# ADC_Board_Single_Board.net
KiCad netlist of a schematic drawn in EAGLE
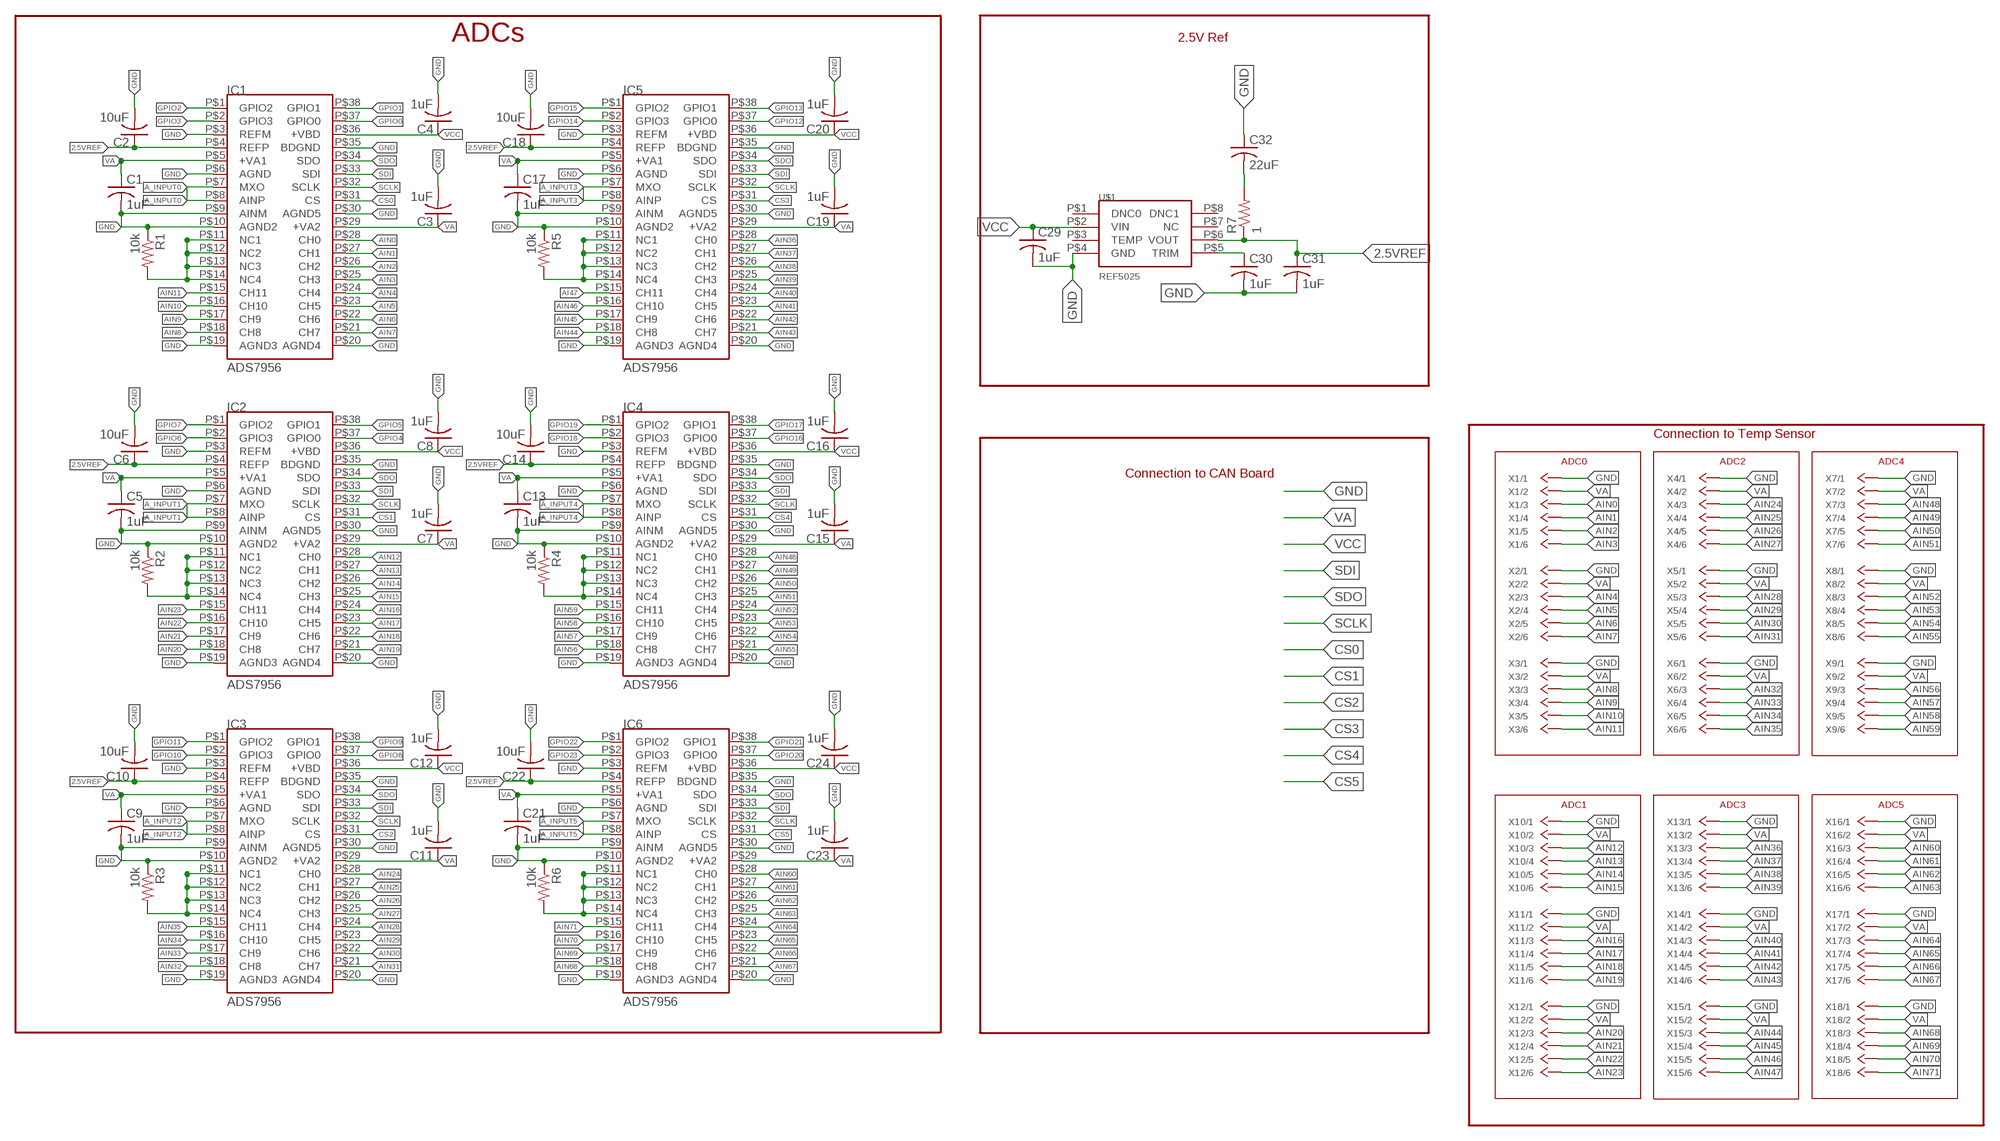
[diagram p0: schematic, sheet 1]

(export (version "E")
  (design (tool "Eeschema 10.0.6"))
  (components
    (comp (ref "C1")
      (value "1uF")
      (footprint "eagle-import:C0603")
      (libsource (lib "eagle-import") (part "C-USC0603"))
    )
    (comp (ref "C2")
      (value "10uF")
      (footprint "eagle-import:C0603")
      (libsource (lib "eagle-import") (part "C-USC0603"))
    )
    (comp (ref "C3")
      (value "1uF")
      (footprint "eagle-import:C0603")
      (libsource (lib "eagle-import") (part "C-USC0603"))
    )
    (comp (ref "C4")
      (value "1uF")
      (footprint "eagle-import:C0603")
      (libsource (lib "eagle-import") (part "C-USC0603"))
    )
    (comp (ref "C5")
      (value "1uF")
      (footprint "eagle-import:C0603")
      (libsource (lib "eagle-import") (part "C-USC0603"))
    )
    (comp (ref "C6")
      (value "10uF")
      (footprint "eagle-import:C0603")
      (libsource (lib "eagle-import") (part "C-USC0603"))
    )
    (comp (ref "C7")
      (value "1uF")
      (footprint "eagle-import:C0603")
      (libsource (lib "eagle-import") (part "C-USC0603"))
    )
    (comp (ref "C8")
      (value "1uF")
      (footprint "eagle-import:C0603")
      (libsource (lib "eagle-import") (part "C-USC0603"))
    )
    (comp (ref "C9")
      (value "1uF")
      (footprint "eagle-import:C0603")
      (libsource (lib "eagle-import") (part "C-USC0603"))
    )
    (comp (ref "C10")
      (value "10uF")
      (footprint "eagle-import:C0603")
      (libsource (lib "eagle-import") (part "C-USC0603"))
    )
    (comp (ref "C11")
      (value "1uF")
      (footprint "eagle-import:C0603")
      (libsource (lib "eagle-import") (part "C-USC0603"))
    )
    (comp (ref "C12")
      (value "1uF")
      (footprint "eagle-import:C0603")
      (libsource (lib "eagle-import") (part "C-USC0603"))
    )
    (comp (ref "C13")
      (value "1uF")
      (footprint "eagle-import:C0603")
      (libsource (lib "eagle-import") (part "C-USC0603"))
    )
    (comp (ref "C14")
      (value "10uF")
      (footprint "eagle-import:C0603")
      (libsource (lib "eagle-import") (part "C-USC0603"))
    )
    (comp (ref "C15")
      (value "1uF")
      (footprint "eagle-import:C0603")
      (libsource (lib "eagle-import") (part "C-USC0603"))
    )
    (comp (ref "C16")
      (value "1uF")
      (footprint "eagle-import:C0603")
      (libsource (lib "eagle-import") (part "C-USC0603"))
    )
    (comp (ref "C17")
      (value "1uF")
      (footprint "eagle-import:C0603")
      (libsource (lib "eagle-import") (part "C-USC0603"))
    )
    (comp (ref "C18")
      (value "10uF")
      (footprint "eagle-import:C0603")
      (libsource (lib "eagle-import") (part "C-USC0603"))
    )
    (comp (ref "C19")
      (value "1uF")
      (footprint "eagle-import:C0603")
      (libsource (lib "eagle-import") (part "C-USC0603"))
    )
    (comp (ref "C20")
      (value "1uF")
      (footprint "eagle-import:C0603")
      (libsource (lib "eagle-import") (part "C-USC0603"))
    )
    (comp (ref "C21")
      (value "1uF")
      (footprint "eagle-import:C0603")
      (libsource (lib "eagle-import") (part "C-USC0603"))
    )
    (comp (ref "C22")
      (value "10uF")
      (footprint "eagle-import:C0603")
      (libsource (lib "eagle-import") (part "C-USC0603"))
    )
    (comp (ref "C23")
      (value "1uF")
      (footprint "eagle-import:C0603")
      (libsource (lib "eagle-import") (part "C-USC0603"))
    )
    (comp (ref "C24")
      (value "1uF")
      (footprint "eagle-import:C0603")
      (libsource (lib "eagle-import") (part "C-USC0603"))
    )
    (comp (ref "C29")
      (value "1uF")
      (footprint "eagle-import:C0603")
      (libsource (lib "eagle-import") (part "C-USC0603"))
    )
    (comp (ref "C30")
      (value "1uF")
      (footprint "eagle-import:C0603")
      (libsource (lib "eagle-import") (part "C-USC0603"))
    )
    (comp (ref "C31")
      (value "1uF")
      (footprint "eagle-import:C0603")
      (libsource (lib "eagle-import") (part "C-USC0603"))
    )
    (comp (ref "C32")
      (value "22uF")
      (footprint "eagle-import:C0603")
      (libsource (lib "eagle-import") (part "C-USC0603"))
    )
    (comp (ref "IC1")
      (value "ADS7956")
      (footprint "eagle-import:TSSOP-38")
      (libsource (lib "eagle-import") (part "ADS7956"))
    )
    (comp (ref "IC2")
      (value "ADS7956")
      (footprint "eagle-import:TSSOP-38")
      (libsource (lib "eagle-import") (part "ADS7956"))
    )
    (comp (ref "IC3")
      (value "ADS7956")
      (footprint "eagle-import:TSSOP-38")
      (libsource (lib "eagle-import") (part "ADS7956"))
    )
    (comp (ref "IC4")
      (value "ADS7956")
      (footprint "eagle-import:TSSOP-38")
      (libsource (lib "eagle-import") (part "ADS7956"))
    )
    (comp (ref "IC5")
      (value "ADS7956")
      (footprint "eagle-import:TSSOP-38")
      (libsource (lib "eagle-import") (part "ADS7956"))
    )
    (comp (ref "IC6")
      (value "ADS7956")
      (footprint "eagle-import:TSSOP-38")
      (libsource (lib "eagle-import") (part "ADS7956"))
    )
    (comp (ref "R1")
      (value "10k")
      (footprint "eagle-import:R0603")
      (libsource (lib "eagle-import") (part "resistor_R-US_R0603"))
    )
    (comp (ref "R2")
      (value "10k")
      (footprint "eagle-import:R0603")
      (libsource (lib "eagle-import") (part "resistor_R-US_R0603"))
    )
    (comp (ref "R3")
      (value "10k")
      (footprint "eagle-import:R0603")
      (libsource (lib "eagle-import") (part "resistor_R-US_R0603"))
    )
    (comp (ref "R4")
      (value "10k")
      (footprint "eagle-import:R0603")
      (libsource (lib "eagle-import") (part "resistor_R-US_R0603"))
    )
    (comp (ref "R5")
      (value "10k")
      (footprint "eagle-import:R0603")
      (libsource (lib "eagle-import") (part "resistor_R-US_R0603"))
    )
    (comp (ref "R6")
      (value "10k")
      (footprint "eagle-import:R0603")
      (libsource (lib "eagle-import") (part "resistor_R-US_R0603"))
    )
    (comp (ref "R7")
      (value "1")
      (footprint "eagle-import:M0805")
      (libsource (lib "eagle-import") (part "R-US_M0805"))
    )
    (comp (ref "U$1")
      (value "REF5025")
      (footprint "eagle-import:TSSOP-8(TI)")
      (libsource (lib "eagle-import") (part "REF5025"))
    )
    (comp (ref "X1")
      (value "6_PIN_CONNTE_IDC")
      (footprint "eagle-import:2178710_IDC")
      (libsource (lib "eagle-import") (part "6_PIN_CONNTE_IDC"))
    )
    (comp (ref "X2")
      (value "6_PIN_CONNTE_IDC")
      (footprint "eagle-import:2178710_IDC")
      (libsource (lib "eagle-import") (part "6_PIN_CONNTE_IDC"))
    )
    (comp (ref "X3")
      (value "6_PIN_CONNTE_IDC")
      (footprint "eagle-import:2178710_IDC")
      (libsource (lib "eagle-import") (part "6_PIN_CONNTE_IDC"))
    )
    (comp (ref "X4")
      (value "6_PIN_CONNTE_IDC")
      (footprint "eagle-import:2178710_IDC")
      (libsource (lib "eagle-import") (part "6_PIN_CONNTE_IDC"))
    )
    (comp (ref "X5")
      (value "6_PIN_CONNTE_IDC")
      (footprint "eagle-import:2178710_IDC")
      (libsource (lib "eagle-import") (part "6_PIN_CONNTE_IDC"))
    )
    (comp (ref "X6")
      (value "6_PIN_CONNTE_IDC")
      (footprint "eagle-import:2178710_IDC")
      (libsource (lib "eagle-import") (part "6_PIN_CONNTE_IDC"))
    )
    (comp (ref "X7")
      (value "6_PIN_CONNTE_IDC")
      (footprint "eagle-import:2178710_IDC")
      (libsource (lib "eagle-import") (part "6_PIN_CONNTE_IDC"))
    )
    (comp (ref "X8")
      (value "6_PIN_CONNTE_IDC")
      (footprint "eagle-import:2178710_IDC")
      (libsource (lib "eagle-import") (part "6_PIN_CONNTE_IDC"))
    )
    (comp (ref "X9")
      (value "6_PIN_CONNTE_IDC")
      (footprint "eagle-import:2178710_IDC")
      (libsource (lib "eagle-import") (part "6_PIN_CONNTE_IDC"))
    )
    (comp (ref "X10")
      (value "6_PIN_CONNTE_IDC")
      (footprint "eagle-import:2178710_IDC")
      (libsource (lib "eagle-import") (part "6_PIN_CONNTE_IDC"))
    )
    (comp (ref "X11")
      (value "6_PIN_CONNTE_IDC")
      (footprint "eagle-import:2178710_IDC")
      (libsource (lib "eagle-import") (part "6_PIN_CONNTE_IDC"))
    )
    (comp (ref "X12")
      (value "6_PIN_CONNTE_IDC")
      (footprint "eagle-import:2178710_IDC")
      (libsource (lib "eagle-import") (part "6_PIN_CONNTE_IDC"))
    )
    (comp (ref "X13")
      (value "6_PIN_CONNTE_IDC")
      (footprint "eagle-import:2178710_IDC")
      (libsource (lib "eagle-import") (part "6_PIN_CONNTE_IDC"))
    )
    (comp (ref "X14")
      (value "6_PIN_CONNTE_IDC")
      (footprint "eagle-import:2178710_IDC")
      (libsource (lib "eagle-import") (part "6_PIN_CONNTE_IDC"))
    )
    (comp (ref "X15")
      (value "6_PIN_CONNTE_IDC")
      (footprint "eagle-import:2178710_IDC")
      (libsource (lib "eagle-import") (part "6_PIN_CONNTE_IDC"))
    )
    (comp (ref "X16")
      (value "6_PIN_CONNTE_IDC")
      (footprint "eagle-import:2178710_IDC")
      (libsource (lib "eagle-import") (part "6_PIN_CONNTE_IDC"))
    )
    (comp (ref "X17")
      (value "6_PIN_CONNTE_IDC")
      (footprint "eagle-import:2178710_IDC")
      (libsource (lib "eagle-import") (part "6_PIN_CONNTE_IDC"))
    )
    (comp (ref "X18")
      (value "6_PIN_CONNTE_IDC")
      (footprint "eagle-import:2178710_IDC")
      (libsource (lib "eagle-import") (part "6_PIN_CONNTE_IDC"))
    )
  )
  (nets
    (net (code "1") (name "2.5VREF") (class "Default")
      (node (ref "C10") (pin "1") (pinfunction "1_1") (pintype "passive"))
      (node (ref "C14") (pin "1") (pinfunction "1_1") (pintype "passive"))
      (node (ref "C18") (pin "1") (pinfunction "1_1") (pintype "passive"))
      (node (ref "C2") (pin "1") (pinfunction "1_1") (pintype "passive"))
      (node (ref "C22") (pin "1") (pinfunction "1_1") (pintype "passive"))
      (node (ref "C31") (pin "1") (pinfunction "1_1") (pintype "passive"))
      (node (ref "C6") (pin "1") (pinfunction "1_1") (pintype "passive"))
      (node (ref "IC1") (pin "P$4") (pinfunction "REFP_P$4") (pintype "bidirectional"))
      (node (ref "IC2") (pin "P$4") (pinfunction "REFP_P$4") (pintype "bidirectional"))
      (node (ref "IC3") (pin "P$4") (pinfunction "REFP_P$4") (pintype "bidirectional"))
      (node (ref "IC4") (pin "P$4") (pinfunction "REFP_P$4") (pintype "bidirectional"))
      (node (ref "IC5") (pin "P$4") (pinfunction "REFP_P$4") (pintype "bidirectional"))
      (node (ref "IC6") (pin "P$4") (pinfunction "REFP_P$4") (pintype "bidirectional"))
      (node (ref "R7") (pin "1") (pinfunction "1_1") (pintype "passive"))
      (node (ref "U$1") (pin "P$6") (pinfunction "VOUT_P$6") (pintype "bidirectional"))
    )
    (net (code "2") (name "AI47") (class "Default")
      (node (ref "IC5") (pin "P$15") (pinfunction "CH11_P$15") (pintype "bidirectional"))
    )
    (net (code "3") (name "AIN0") (class "Default")
      (node (ref "IC1") (pin "P$28") (pinfunction "CH0_P$28") (pintype "bidirectional"))
      (node (ref "X1") (pin "P$3") (pinfunction "$/1_P$3") (pintype "bidirectional"))
    )
    (net (code "4") (name "AIN1") (class "Default")
      (node (ref "IC1") (pin "P$27") (pinfunction "CH1_P$27") (pintype "bidirectional"))
      (node (ref "X1") (pin "P$4") (pinfunction "$/1_P$4") (pintype "bidirectional"))
    )
    (net (code "5") (name "AIN2") (class "Default")
      (node (ref "IC1") (pin "P$26") (pinfunction "CH2_P$26") (pintype "bidirectional"))
      (node (ref "X1") (pin "P$5") (pinfunction "$/1_P$5") (pintype "bidirectional"))
    )
    (net (code "6") (name "AIN3") (class "Default")
      (node (ref "IC1") (pin "P$25") (pinfunction "CH3_P$25") (pintype "bidirectional"))
      (node (ref "X1") (pin "P$6") (pinfunction "$/1_P$6") (pintype "bidirectional"))
    )
    (net (code "7") (name "AIN4") (class "Default")
      (node (ref "IC1") (pin "P$24") (pinfunction "CH4_P$24") (pintype "bidirectional"))
      (node (ref "X2") (pin "P$3") (pinfunction "$/1_P$3") (pintype "bidirectional"))
    )
    (net (code "8") (name "AIN5") (class "Default")
      (node (ref "IC1") (pin "P$23") (pinfunction "CH5_P$23") (pintype "bidirectional"))
      (node (ref "X2") (pin "P$4") (pinfunction "$/1_P$4") (pintype "bidirectional"))
    )
    (net (code "9") (name "AIN6") (class "Default")
      (node (ref "IC1") (pin "P$22") (pinfunction "CH6_P$22") (pintype "bidirectional"))
      (node (ref "X2") (pin "P$5") (pinfunction "$/1_P$5") (pintype "bidirectional"))
    )
    (net (code "10") (name "AIN7") (class "Default")
      (node (ref "IC1") (pin "P$21") (pinfunction "CH7_P$21") (pintype "bidirectional"))
      (node (ref "X2") (pin "P$6") (pinfunction "$/1_P$6") (pintype "bidirectional"))
    )
    (net (code "11") (name "AIN8") (class "Default")
      (node (ref "IC1") (pin "P$18") (pinfunction "CH8_P$18") (pintype "bidirectional"))
      (node (ref "X3") (pin "P$3") (pinfunction "$/1_P$3") (pintype "bidirectional"))
    )
    (net (code "12") (name "AIN9") (class "Default")
      (node (ref "IC1") (pin "P$17") (pinfunction "CH9_P$17") (pintype "bidirectional"))
      (node (ref "X3") (pin "P$4") (pinfunction "$/1_P$4") (pintype "bidirectional"))
    )
    (net (code "13") (name "AIN10") (class "Default")
      (node (ref "IC1") (pin "P$16") (pinfunction "CH10_P$16") (pintype "bidirectional"))
      (node (ref "X3") (pin "P$5") (pinfunction "$/1_P$5") (pintype "bidirectional"))
    )
    (net (code "14") (name "AIN11") (class "Default")
      (node (ref "IC1") (pin "P$15") (pinfunction "CH11_P$15") (pintype "bidirectional"))
      (node (ref "X3") (pin "P$6") (pinfunction "$/1_P$6") (pintype "bidirectional"))
    )
    (net (code "15") (name "AIN12") (class "Default")
      (node (ref "IC2") (pin "P$28") (pinfunction "CH0_P$28") (pintype "bidirectional"))
      (node (ref "X10") (pin "P$3") (pinfunction "$/1_P$3") (pintype "bidirectional"))
    )
    (net (code "16") (name "AIN13") (class "Default")
      (node (ref "IC2") (pin "P$27") (pinfunction "CH1_P$27") (pintype "bidirectional"))
      (node (ref "X10") (pin "P$4") (pinfunction "$/1_P$4") (pintype "bidirectional"))
    )
    (net (code "17") (name "AIN14") (class "Default")
      (node (ref "IC2") (pin "P$26") (pinfunction "CH2_P$26") (pintype "bidirectional"))
      (node (ref "X10") (pin "P$5") (pinfunction "$/1_P$5") (pintype "bidirectional"))
    )
    (net (code "18") (name "AIN15") (class "Default")
      (node (ref "IC2") (pin "P$25") (pinfunction "CH3_P$25") (pintype "bidirectional"))
      (node (ref "X10") (pin "P$6") (pinfunction "$/1_P$6") (pintype "bidirectional"))
    )
    (net (code "19") (name "AIN16") (class "Default")
      (node (ref "IC2") (pin "P$24") (pinfunction "CH4_P$24") (pintype "bidirectional"))
      (node (ref "X11") (pin "P$3") (pinfunction "$/1_P$3") (pintype "bidirectional"))
    )
    (net (code "20") (name "AIN17") (class "Default")
      (node (ref "IC2") (pin "P$23") (pinfunction "CH5_P$23") (pintype "bidirectional"))
      (node (ref "X11") (pin "P$4") (pinfunction "$/1_P$4") (pintype "bidirectional"))
    )
    (net (code "21") (name "AIN18") (class "Default")
      (node (ref "IC2") (pin "P$22") (pinfunction "CH6_P$22") (pintype "bidirectional"))
      (node (ref "X11") (pin "P$5") (pinfunction "$/1_P$5") (pintype "bidirectional"))
    )
    (net (code "22") (name "AIN19") (class "Default")
      (node (ref "IC2") (pin "P$21") (pinfunction "CH7_P$21") (pintype "bidirectional"))
      (node (ref "X11") (pin "P$6") (pinfunction "$/1_P$6") (pintype "bidirectional"))
    )
    (net (code "23") (name "AIN20") (class "Default")
      (node (ref "IC2") (pin "P$18") (pinfunction "CH8_P$18") (pintype "bidirectional"))
      (node (ref "X12") (pin "P$3") (pinfunction "$/1_P$3") (pintype "bidirectional"))
    )
    (net (code "24") (name "AIN21") (class "Default")
      (node (ref "IC2") (pin "P$17") (pinfunction "CH9_P$17") (pintype "bidirectional"))
      (node (ref "X12") (pin "P$4") (pinfunction "$/1_P$4") (pintype "bidirectional"))
    )
    (net (code "25") (name "AIN22") (class "Default")
      (node (ref "IC2") (pin "P$16") (pinfunction "CH10_P$16") (pintype "bidirectional"))
      (node (ref "X12") (pin "P$5") (pinfunction "$/1_P$5") (pintype "bidirectional"))
    )
    (net (code "26") (name "AIN23") (class "Default")
      (node (ref "IC2") (pin "P$15") (pinfunction "CH11_P$15") (pintype "bidirectional"))
      (node (ref "X12") (pin "P$6") (pinfunction "$/1_P$6") (pintype "bidirectional"))
    )
    (net (code "27") (name "AIN24") (class "Default")
      (node (ref "IC3") (pin "P$28") (pinfunction "CH0_P$28") (pintype "bidirectional"))
      (node (ref "X4") (pin "P$3") (pinfunction "$/1_P$3") (pintype "bidirectional"))
    )
    (net (code "28") (name "AIN25") (class "Default")
      (node (ref "IC3") (pin "P$27") (pinfunction "CH1_P$27") (pintype "bidirectional"))
      (node (ref "X4") (pin "P$4") (pinfunction "$/1_P$4") (pintype "bidirectional"))
    )
    (net (code "29") (name "AIN26") (class "Default")
      (node (ref "IC3") (pin "P$26") (pinfunction "CH2_P$26") (pintype "bidirectional"))
      (node (ref "X4") (pin "P$5") (pinfunction "$/1_P$5") (pintype "bidirectional"))
    )
    (net (code "30") (name "AIN27") (class "Default")
      (node (ref "IC3") (pin "P$25") (pinfunction "CH3_P$25") (pintype "bidirectional"))
      (node (ref "X4") (pin "P$6") (pinfunction "$/1_P$6") (pintype "bidirectional"))
    )
    (net (code "31") (name "AIN28") (class "Default")
      (node (ref "IC3") (pin "P$24") (pinfunction "CH4_P$24") (pintype "bidirectional"))
      (node (ref "X5") (pin "P$3") (pinfunction "$/1_P$3") (pintype "bidirectional"))
    )
    (net (code "32") (name "AIN29") (class "Default")
      (node (ref "IC3") (pin "P$23") (pinfunction "CH5_P$23") (pintype "bidirectional"))
      (node (ref "X5") (pin "P$4") (pinfunction "$/1_P$4") (pintype "bidirectional"))
    )
    (net (code "33") (name "AIN30") (class "Default")
      (node (ref "IC3") (pin "P$22") (pinfunction "CH6_P$22") (pintype "bidirectional"))
      (node (ref "X5") (pin "P$5") (pinfunction "$/1_P$5") (pintype "bidirectional"))
    )
    (net (code "34") (name "AIN31") (class "Default")
      (node (ref "IC3") (pin "P$21") (pinfunction "CH7_P$21") (pintype "bidirectional"))
      (node (ref "X5") (pin "P$6") (pinfunction "$/1_P$6") (pintype "bidirectional"))
    )
    (net (code "35") (name "AIN32") (class "Default")
      (node (ref "IC3") (pin "P$18") (pinfunction "CH8_P$18") (pintype "bidirectional"))
      (node (ref "X6") (pin "P$3") (pinfunction "$/1_P$3") (pintype "bidirectional"))
    )
    (net (code "36") (name "AIN33") (class "Default")
      (node (ref "IC3") (pin "P$17") (pinfunction "CH9_P$17") (pintype "bidirectional"))
      (node (ref "X6") (pin "P$4") (pinfunction "$/1_P$4") (pintype "bidirectional"))
    )
    (net (code "37") (name "AIN34") (class "Default")
      (node (ref "IC3") (pin "P$16") (pinfunction "CH10_P$16") (pintype "bidirectional"))
      (node (ref "X6") (pin "P$5") (pinfunction "$/1_P$5") (pintype "bidirectional"))
    )
    (net (code "38") (name "AIN35") (class "Default")
      (node (ref "IC3") (pin "P$15") (pinfunction "CH11_P$15") (pintype "bidirectional"))
      (node (ref "X6") (pin "P$6") (pinfunction "$/1_P$6") (pintype "bidirectional"))
    )
    (net (code "39") (name "AIN36") (class "Default")
      (node (ref "IC5") (pin "P$28") (pinfunction "CH0_P$28") (pintype "bidirectional"))
      (node (ref "X13") (pin "P$3") (pinfunction "$/1_P$3") (pintype "bidirectional"))
    )
    (net (code "40") (name "AIN37") (class "Default")
      (node (ref "IC5") (pin "P$27") (pinfunction "CH1_P$27") (pintype "bidirectional"))
      (node (ref "X13") (pin "P$4") (pinfunction "$/1_P$4") (pintype "bidirectional"))
    )
    (net (code "41") (name "AIN38") (class "Default")
      (node (ref "IC5") (pin "P$26") (pinfunction "CH2_P$26") (pintype "bidirectional"))
      (node (ref "X13") (pin "P$5") (pinfunction "$/1_P$5") (pintype "bidirectional"))
    )
    (net (code "42") (name "AIN39") (class "Default")
      (node (ref "IC5") (pin "P$25") (pinfunction "CH3_P$25") (pintype "bidirectional"))
      (node (ref "X13") (pin "P$6") (pinfunction "$/1_P$6") (pintype "bidirectional"))
    )
    (net (code "43") (name "AIN40") (class "Default")
      (node (ref "IC5") (pin "P$24") (pinfunction "CH4_P$24") (pintype "bidirectional"))
      (node (ref "X14") (pin "P$3") (pinfunction "$/1_P$3") (pintype "bidirectional"))
    )
    (net (code "44") (name "AIN41") (class "Default")
      (node (ref "IC5") (pin "P$23") (pinfunction "CH5_P$23") (pintype "bidirectional"))
      (node (ref "X14") (pin "P$4") (pinfunction "$/1_P$4") (pintype "bidirectional"))
    )
    (net (code "45") (name "AIN42") (class "Default")
      (node (ref "IC5") (pin "P$22") (pinfunction "CH6_P$22") (pintype "bidirectional"))
      (node (ref "X14") (pin "P$5") (pinfunction "$/1_P$5") (pintype "bidirectional"))
    )
    (net (code "46") (name "AIN43") (class "Default")
      (node (ref "IC5") (pin "P$21") (pinfunction "CH7_P$21") (pintype "bidirectional"))
      (node (ref "X14") (pin "P$6") (pinfunction "$/1_P$6") (pintype "bidirectional"))
    )
    (net (code "47") (name "AIN44") (class "Default")
      (node (ref "IC5") (pin "P$18") (pinfunction "CH8_P$18") (pintype "bidirectional"))
      (node (ref "X15") (pin "P$3") (pinfunction "$/1_P$3") (pintype "bidirectional"))
    )
    (net (code "48") (name "AIN45") (class "Default")
      (node (ref "IC5") (pin "P$17") (pinfunction "CH9_P$17") (pintype "bidirectional"))
      (node (ref "X15") (pin "P$4") (pinfunction "$/1_P$4") (pintype "bidirectional"))
    )
    (net (code "49") (name "AIN46") (class "Default")
      (node (ref "IC5") (pin "P$16") (pinfunction "CH10_P$16") (pintype "bidirectional"))
      (node (ref "X15") (pin "P$5") (pinfunction "$/1_P$5") (pintype "bidirectional"))
    )
    (net (code "50") (name "AIN47") (class "Default")
      (node (ref "X15") (pin "P$6") (pinfunction "$/1_P$6") (pintype "bidirectional"))
    )
    (net (code "51") (name "AIN48") (class "Default")
      (node (ref "IC4") (pin "P$28") (pinfunction "CH0_P$28") (pintype "bidirectional"))
      (node (ref "X7") (pin "P$3") (pinfunction "$/1_P$3") (pintype "bidirectional"))
    )
    (net (code "52") (name "AIN49") (class "Default")
      (node (ref "IC4") (pin "P$27") (pinfunction "CH1_P$27") (pintype "bidirectional"))
      (node (ref "X7") (pin "P$4") (pinfunction "$/1_P$4") (pintype "bidirectional"))
    )
    (net (code "53") (name "AIN50") (class "Default")
      (node (ref "IC4") (pin "P$26") (pinfunction "CH2_P$26") (pintype "bidirectional"))
      (node (ref "X7") (pin "P$5") (pinfunction "$/1_P$5") (pintype "bidirectional"))
    )
    (net (code "54") (name "AIN51") (class "Default")
      (node (ref "IC4") (pin "P$25") (pinfunction "CH3_P$25") (pintype "bidirectional"))
      (node (ref "X7") (pin "P$6") (pinfunction "$/1_P$6") (pintype "bidirectional"))
    )
    (net (code "55") (name "AIN52") (class "Default")
      (node (ref "IC4") (pin "P$24") (pinfunction "CH4_P$24") (pintype "bidirectional"))
      (node (ref "X8") (pin "P$3") (pinfunction "$/1_P$3") (pintype "bidirectional"))
    )
    (net (code "56") (name "AIN53") (class "Default")
      (node (ref "IC4") (pin "P$23") (pinfunction "CH5_P$23") (pintype "bidirectional"))
      (node (ref "X8") (pin "P$4") (pinfunction "$/1_P$4") (pintype "bidirectional"))
    )
    (net (code "57") (name "AIN54") (class "Default")
      (node (ref "IC4") (pin "P$22") (pinfunction "CH6_P$22") (pintype "bidirectional"))
      (node (ref "X8") (pin "P$5") (pinfunction "$/1_P$5") (pintype "bidirectional"))
    )
    (net (code "58") (name "AIN55") (class "Default")
      (node (ref "IC4") (pin "P$21") (pinfunction "CH7_P$21") (pintype "bidirectional"))
      (node (ref "X8") (pin "P$6") (pinfunction "$/1_P$6") (pintype "bidirectional"))
    )
    (net (code "59") (name "AIN56") (class "Default")
      (node (ref "IC4") (pin "P$18") (pinfunction "CH8_P$18") (pintype "bidirectional"))
      (node (ref "X9") (pin "P$3") (pinfunction "$/1_P$3") (pintype "bidirectional"))
    )
    (net (code "60") (name "AIN57") (class "Default")
      (node (ref "IC4") (pin "P$17") (pinfunction "CH9_P$17") (pintype "bidirectional"))
      (node (ref "X9") (pin "P$4") (pinfunction "$/1_P$4") (pintype "bidirectional"))
    )
    (net (code "61") (name "AIN58") (class "Default")
      (node (ref "IC4") (pin "P$16") (pinfunction "CH10_P$16") (pintype "bidirectional"))
      (node (ref "X9") (pin "P$5") (pinfunction "$/1_P$5") (pintype "bidirectional"))
    )
    (net (code "62") (name "AIN59") (class "Default")
      (node (ref "IC4") (pin "P$15") (pinfunction "CH11_P$15") (pintype "bidirectional"))
      (node (ref "X9") (pin "P$6") (pinfunction "$/1_P$6") (pintype "bidirectional"))
    )
    (net (code "63") (name "AIN60") (class "Default")
      (node (ref "IC6") (pin "P$28") (pinfunction "CH0_P$28") (pintype "bidirectional"))
      (node (ref "X16") (pin "P$3") (pinfunction "$/1_P$3") (pintype "bidirectional"))
    )
    (net (code "64") (name "AIN61") (class "Default")
      (node (ref "IC6") (pin "P$27") (pinfunction "CH1_P$27") (pintype "bidirectional"))
      (node (ref "X16") (pin "P$4") (pinfunction "$/1_P$4") (pintype "bidirectional"))
    )
    (net (code "65") (name "AIN62") (class "Default")
      (node (ref "IC6") (pin "P$26") (pinfunction "CH2_P$26") (pintype "bidirectional"))
      (node (ref "X16") (pin "P$5") (pinfunction "$/1_P$5") (pintype "bidirectional"))
    )
    (net (code "66") (name "AIN63") (class "Default")
      (node (ref "IC6") (pin "P$25") (pinfunction "CH3_P$25") (pintype "bidirectional"))
      (node (ref "X16") (pin "P$6") (pinfunction "$/1_P$6") (pintype "bidirectional"))
    )
    (net (code "67") (name "AIN64") (class "Default")
      (node (ref "IC6") (pin "P$24") (pinfunction "CH4_P$24") (pintype "bidirectional"))
      (node (ref "X17") (pin "P$3") (pinfunction "$/1_P$3") (pintype "bidirectional"))
    )
    (net (code "68") (name "AIN65") (class "Default")
      (node (ref "IC6") (pin "P$23") (pinfunction "CH5_P$23") (pintype "bidirectional"))
      (node (ref "X17") (pin "P$4") (pinfunction "$/1_P$4") (pintype "bidirectional"))
    )
    (net (code "69") (name "AIN66") (class "Default")
      (node (ref "IC6") (pin "P$22") (pinfunction "CH6_P$22") (pintype "bidirectional"))
      (node (ref "X17") (pin "P$5") (pinfunction "$/1_P$5") (pintype "bidirectional"))
    )
    (net (code "70") (name "AIN67") (class "Default")
      (node (ref "IC6") (pin "P$21") (pinfunction "CH7_P$21") (pintype "bidirectional"))
      (node (ref "X17") (pin "P$6") (pinfunction "$/1_P$6") (pintype "bidirectional"))
    )
    (net (code "71") (name "AIN68") (class "Default")
      (node (ref "IC6") (pin "P$18") (pinfunction "CH8_P$18") (pintype "bidirectional"))
      (node (ref "X18") (pin "P$3") (pinfunction "$/1_P$3") (pintype "bidirectional"))
    )
    (net (code "72") (name "AIN69") (class "Default")
      (node (ref "IC6") (pin "P$17") (pinfunction "CH9_P$17") (pintype "bidirectional"))
      (node (ref "X18") (pin "P$4") (pinfunction "$/1_P$4") (pintype "bidirectional"))
    )
    (net (code "73") (name "AIN70") (class "Default")
      (node (ref "IC6") (pin "P$16") (pinfunction "CH10_P$16") (pintype "bidirectional"))
      (node (ref "X18") (pin "P$5") (pinfunction "$/1_P$5") (pintype "bidirectional"))
    )
    (net (code "74") (name "AIN71") (class "Default")
      (node (ref "IC6") (pin "P$15") (pinfunction "CH11_P$15") (pintype "bidirectional"))
      (node (ref "X18") (pin "P$6") (pinfunction "$/1_P$6") (pintype "bidirectional"))
    )
    (net (code "75") (name "A_INPUT0") (class "Default")
      (node (ref "IC1") (pin "P$7") (pinfunction "MXO_P$7") (pintype "bidirectional"))
      (node (ref "IC1") (pin "P$8") (pinfunction "AINP_P$8") (pintype "bidirectional"))
    )
    (net (code "76") (name "A_INPUT1") (class "Default")
      (node (ref "IC2") (pin "P$7") (pinfunction "MXO_P$7") (pintype "bidirectional"))
      (node (ref "IC2") (pin "P$8") (pinfunction "AINP_P$8") (pintype "bidirectional"))
    )
    (net (code "77") (name "A_INPUT2") (class "Default")
      (node (ref "IC3") (pin "P$7") (pinfunction "MXO_P$7") (pintype "bidirectional"))
      (node (ref "IC3") (pin "P$8") (pinfunction "AINP_P$8") (pintype "bidirectional"))
    )
    (net (code "78") (name "A_INPUT3") (class "Default")
      (node (ref "IC5") (pin "P$7") (pinfunction "MXO_P$7") (pintype "bidirectional"))
      (node (ref "IC5") (pin "P$8") (pinfunction "AINP_P$8") (pintype "bidirectional"))
    )
    (net (code "79") (name "A_INPUT4") (class "Default")
      (node (ref "IC4") (pin "P$7") (pinfunction "MXO_P$7") (pintype "bidirectional"))
      (node (ref "IC4") (pin "P$8") (pinfunction "AINP_P$8") (pintype "bidirectional"))
    )
    (net (code "80") (name "A_INPUT5") (class "Default")
      (node (ref "IC6") (pin "P$7") (pinfunction "MXO_P$7") (pintype "bidirectional"))
      (node (ref "IC6") (pin "P$8") (pinfunction "AINP_P$8") (pintype "bidirectional"))
    )
    (net (code "81") (name "CS0") (class "Default")
      (node (ref "IC1") (pin "P$31") (pinfunction "CS_P$31") (pintype "bidirectional"))
    )
    (net (code "82") (name "CS1") (class "Default")
      (node (ref "IC2") (pin "P$31") (pinfunction "CS_P$31") (pintype "bidirectional"))
    )
    (net (code "83") (name "CS2") (class "Default")
      (node (ref "IC3") (pin "P$31") (pinfunction "CS_P$31") (pintype "bidirectional"))
    )
    (net (code "84") (name "CS3") (class "Default")
      (node (ref "IC5") (pin "P$31") (pinfunction "CS_P$31") (pintype "bidirectional"))
    )
    (net (code "85") (name "CS4") (class "Default")
      (node (ref "IC4") (pin "P$31") (pinfunction "CS_P$31") (pintype "bidirectional"))
    )
    (net (code "86") (name "CS5") (class "Default")
      (node (ref "IC6") (pin "P$31") (pinfunction "CS_P$31") (pintype "bidirectional"))
    )
    (net (code "87") (name "GND") (class "Default")
      (node (ref "C1") (pin "2") (pinfunction "2_2") (pintype "passive"))
      (node (ref "C10") (pin "2") (pinfunction "2_2") (pintype "passive"))
      (node (ref "C11") (pin "2") (pinfunction "2_2") (pintype "passive"))
      (node (ref "C12") (pin "2") (pinfunction "2_2") (pintype "passive"))
      (node (ref "C13") (pin "2") (pinfunction "2_2") (pintype "passive"))
      (node (ref "C14") (pin "2") (pinfunction "2_2") (pintype "passive"))
      (node (ref "C15") (pin "2") (pinfunction "2_2") (pintype "passive"))
      (node (ref "C16") (pin "2") (pinfunction "2_2") (pintype "passive"))
      (node (ref "C17") (pin "2") (pinfunction "2_2") (pintype "passive"))
      (node (ref "C18") (pin "2") (pinfunction "2_2") (pintype "passive"))
      (node (ref "C19") (pin "2") (pinfunction "2_2") (pintype "passive"))
      (node (ref "C2") (pin "2") (pinfunction "2_2") (pintype "passive"))
      (node (ref "C20") (pin "2") (pinfunction "2_2") (pintype "passive"))
      (node (ref "C21") (pin "2") (pinfunction "2_2") (pintype "passive"))
      (node (ref "C22") (pin "2") (pinfunction "2_2") (pintype "passive"))
      (node (ref "C23") (pin "2") (pinfunction "2_2") (pintype "passive"))
      (node (ref "C24") (pin "2") (pinfunction "2_2") (pintype "passive"))
      (node (ref "C29") (pin "2") (pinfunction "2_2") (pintype "passive"))
      (node (ref "C3") (pin "2") (pinfunction "2_2") (pintype "passive"))
      (node (ref "C30") (pin "2") (pinfunction "2_2") (pintype "passive"))
      (node (ref "C31") (pin "2") (pinfunction "2_2") (pintype "passive"))
      (node (ref "C32") (pin "1") (pinfunction "1_1") (pintype "passive"))
      (node (ref "C4") (pin "2") (pinfunction "2_2") (pintype "passive"))
      (node (ref "C5") (pin "2") (pinfunction "2_2") (pintype "passive"))
      (node (ref "C6") (pin "2") (pinfunction "2_2") (pintype "passive"))
      (node (ref "C7") (pin "2") (pinfunction "2_2") (pintype "passive"))
      (node (ref "C8") (pin "2") (pinfunction "2_2") (pintype "passive"))
      (node (ref "C9") (pin "2") (pinfunction "2_2") (pintype "passive"))
      (node (ref "IC1") (pin "P$10") (pinfunction "AGND2_P$10") (pintype "bidirectional"))
      (node (ref "IC1") (pin "P$19") (pinfunction "AGND3_P$19") (pintype "bidirectional"))
      (node (ref "IC1") (pin "P$20") (pinfunction "AGND4_P$20") (pintype "bidirectional"))
      (node (ref "IC1") (pin "P$3") (pinfunction "REFM_P$3") (pintype "bidirectional"))
      (node (ref "IC1") (pin "P$30") (pinfunction "AGND5_P$30") (pintype "bidirectional"))
      (node (ref "IC1") (pin "P$35") (pinfunction "BDGND_P$35") (pintype "bidirectional"))
      (node (ref "IC1") (pin "P$6") (pinfunction "AGND_P$6") (pintype "bidirectional"))
      (node (ref "IC1") (pin "P$9") (pinfunction "AINM_P$9") (pintype "bidirectional"))
      (node (ref "IC2") (pin "P$10") (pinfunction "AGND2_P$10") (pintype "bidirectional"))
      (node (ref "IC2") (pin "P$19") (pinfunction "AGND3_P$19") (pintype "bidirectional"))
      (node (ref "IC2") (pin "P$20") (pinfunction "AGND4_P$20") (pintype "bidirectional"))
      (node (ref "IC2") (pin "P$3") (pinfunction "REFM_P$3") (pintype "bidirectional"))
      (node (ref "IC2") (pin "P$30") (pinfunction "AGND5_P$30") (pintype "bidirectional"))
      (node (ref "IC2") (pin "P$35") (pinfunction "BDGND_P$35") (pintype "bidirectional"))
      (node (ref "IC2") (pin "P$6") (pinfunction "AGND_P$6") (pintype "bidirectional"))
      (node (ref "IC2") (pin "P$9") (pinfunction "AINM_P$9") (pintype "bidirectional"))
      (node (ref "IC3") (pin "P$10") (pinfunction "AGND2_P$10") (pintype "bidirectional"))
      (node (ref "IC3") (pin "P$19") (pinfunction "AGND3_P$19") (pintype "bidirectional"))
      (node (ref "IC3") (pin "P$20") (pinfunction "AGND4_P$20") (pintype "bidirectional"))
      (node (ref "IC3") (pin "P$3") (pinfunction "REFM_P$3") (pintype "bidirectional"))
      (node (ref "IC3") (pin "P$30") (pinfunction "AGND5_P$30") (pintype "bidirectional"))
      (node (ref "IC3") (pin "P$35") (pinfunction "BDGND_P$35") (pintype "bidirectional"))
      (node (ref "IC3") (pin "P$6") (pinfunction "AGND_P$6") (pintype "bidirectional"))
      (node (ref "IC3") (pin "P$9") (pinfunction "AINM_P$9") (pintype "bidirectional"))
      (node (ref "IC4") (pin "P$10") (pinfunction "AGND2_P$10") (pintype "bidirectional"))
      (node (ref "IC4") (pin "P$19") (pinfunction "AGND3_P$19") (pintype "bidirectional"))
      (node (ref "IC4") (pin "P$20") (pinfunction "AGND4_P$20") (pintype "bidirectional"))
      (node (ref "IC4") (pin "P$3") (pinfunction "REFM_P$3") (pintype "bidirectional"))
      (node (ref "IC4") (pin "P$30") (pinfunction "AGND5_P$30") (pintype "bidirectional"))
      (node (ref "IC4") (pin "P$35") (pinfunction "BDGND_P$35") (pintype "bidirectional"))
      (node (ref "IC4") (pin "P$6") (pinfunction "AGND_P$6") (pintype "bidirectional"))
      (node (ref "IC4") (pin "P$9") (pinfunction "AINM_P$9") (pintype "bidirectional"))
      (node (ref "IC5") (pin "P$10") (pinfunction "AGND2_P$10") (pintype "bidirectional"))
      (node (ref "IC5") (pin "P$19") (pinfunction "AGND3_P$19") (pintype "bidirectional"))
      (node (ref "IC5") (pin "P$20") (pinfunction "AGND4_P$20") (pintype "bidirectional"))
      (node (ref "IC5") (pin "P$3") (pinfunction "REFM_P$3") (pintype "bidirectional"))
      (node (ref "IC5") (pin "P$30") (pinfunction "AGND5_P$30") (pintype "bidirectional"))
      (node (ref "IC5") (pin "P$35") (pinfunction "BDGND_P$35") (pintype "bidirectional"))
      (node (ref "IC5") (pin "P$6") (pinfunction "AGND_P$6") (pintype "bidirectional"))
      (node (ref "IC5") (pin "P$9") (pinfunction "AINM_P$9") (pintype "bidirectional"))
      (node (ref "IC6") (pin "P$10") (pinfunction "AGND2_P$10") (pintype "bidirectional"))
      (node (ref "IC6") (pin "P$19") (pinfunction "AGND3_P$19") (pintype "bidirectional"))
      (node (ref "IC6") (pin "P$20") (pinfunction "AGND4_P$20") (pintype "bidirectional"))
      (node (ref "IC6") (pin "P$3") (pinfunction "REFM_P$3") (pintype "bidirectional"))
      (node (ref "IC6") (pin "P$30") (pinfunction "AGND5_P$30") (pintype "bidirectional"))
      (node (ref "IC6") (pin "P$35") (pinfunction "BDGND_P$35") (pintype "bidirectional"))
      (node (ref "IC6") (pin "P$6") (pinfunction "AGND_P$6") (pintype "bidirectional"))
      (node (ref "IC6") (pin "P$9") (pinfunction "AINM_P$9") (pintype "bidirectional"))
      (node (ref "R1") (pin "1") (pinfunction "1_1") (pintype "passive"))
      (node (ref "R2") (pin "1") (pinfunction "1_1") (pintype "passive"))
      (node (ref "R3") (pin "1") (pinfunction "1_1") (pintype "passive"))
      (node (ref "R4") (pin "1") (pinfunction "1_1") (pintype "passive"))
      (node (ref "R5") (pin "1") (pinfunction "1_1") (pintype "passive"))
      (node (ref "R6") (pin "1") (pinfunction "1_1") (pintype "passive"))
      (node (ref "U$1") (pin "P$4") (pinfunction "GND_P$4") (pintype "bidirectional"))
      (node (ref "X1") (pin "P$1") (pinfunction "$/1_P$1") (pintype "bidirectional"))
      (node (ref "X10") (pin "P$1") (pinfunction "$/1_P$1") (pintype "bidirectional"))
      (node (ref "X11") (pin "P$1") (pinfunction "$/1_P$1") (pintype "bidirectional"))
      (node (ref "X12") (pin "P$1") (pinfunction "$/1_P$1") (pintype "bidirectional"))
      (node (ref "X13") (pin "P$1") (pinfunction "$/1_P$1") (pintype "bidirectional"))
      (node (ref "X14") (pin "P$1") (pinfunction "$/1_P$1") (pintype "bidirectional"))
      (node (ref "X15") (pin "P$1") (pinfunction "$/1_P$1") (pintype "bidirectional"))
      (node (ref "X16") (pin "P$1") (pinfunction "$/1_P$1") (pintype "bidirectional"))
      (node (ref "X17") (pin "P$1") (pinfunction "$/1_P$1") (pintype "bidirectional"))
      (node (ref "X18") (pin "P$1") (pinfunction "$/1_P$1") (pintype "bidirectional"))
      (node (ref "X2") (pin "P$1") (pinfunction "$/1_P$1") (pintype "bidirectional"))
      (node (ref "X3") (pin "P$1") (pinfunction "$/1_P$1") (pintype "bidirectional"))
      (node (ref "X4") (pin "P$1") (pinfunction "$/1_P$1") (pintype "bidirectional"))
      (node (ref "X5") (pin "P$1") (pinfunction "$/1_P$1") (pintype "bidirectional"))
      (node (ref "X6") (pin "P$1") (pinfunction "$/1_P$1") (pintype "bidirectional"))
      (node (ref "X7") (pin "P$1") (pinfunction "$/1_P$1") (pintype "bidirectional"))
      (node (ref "X8") (pin "P$1") (pinfunction "$/1_P$1") (pintype "bidirectional"))
      (node (ref "X9") (pin "P$1") (pinfunction "$/1_P$1") (pintype "bidirectional"))
    )
    (net (code "88") (name "GPIO0") (class "Default")
      (node (ref "IC1") (pin "P$37") (pinfunction "GPIO0_P$37") (pintype "bidirectional"))
    )
    (net (code "89") (name "GPIO1") (class "Default")
      (node (ref "IC1") (pin "P$38") (pinfunction "GPIO1_P$38") (pintype "bidirectional"))
    )
    (net (code "90") (name "GPIO2") (class "Default")
      (node (ref "IC1") (pin "P$1") (pinfunction "GPIO2_P$1") (pintype "bidirectional"))
    )
    (net (code "91") (name "GPIO3") (class "Default")
      (node (ref "IC1") (pin "P$2") (pinfunction "GPIO3_P$2") (pintype "bidirectional"))
    )
    (net (code "92") (name "GPIO4") (class "Default")
      (node (ref "IC2") (pin "P$37") (pinfunction "GPIO0_P$37") (pintype "bidirectional"))
    )
    (net (code "93") (name "GPIO5") (class "Default")
      (node (ref "IC2") (pin "P$38") (pinfunction "GPIO1_P$38") (pintype "bidirectional"))
    )
    (net (code "94") (name "GPIO6") (class "Default")
      (node (ref "IC2") (pin "P$2") (pinfunction "GPIO3_P$2") (pintype "bidirectional"))
    )
    (net (code "95") (name "GPIO7") (class "Default")
      (node (ref "IC2") (pin "P$1") (pinfunction "GPIO2_P$1") (pintype "bidirectional"))
    )
    (net (code "96") (name "GPIO8") (class "Default")
      (node (ref "IC3") (pin "P$37") (pinfunction "GPIO0_P$37") (pintype "bidirectional"))
    )
    (net (code "97") (name "GPIO9") (class "Default")
      (node (ref "IC3") (pin "P$38") (pinfunction "GPIO1_P$38") (pintype "bidirectional"))
    )
    (net (code "98") (name "GPIO10") (class "Default")
      (node (ref "IC3") (pin "P$2") (pinfunction "GPIO3_P$2") (pintype "bidirectional"))
    )
    (net (code "99") (name "GPIO11") (class "Default")
      (node (ref "IC3") (pin "P$1") (pinfunction "GPIO2_P$1") (pintype "bidirectional"))
    )
    (net (code "100") (name "GPIO12") (class "Default")
      (node (ref "IC5") (pin "P$37") (pinfunction "GPIO0_P$37") (pintype "bidirectional"))
    )
    (net (code "101") (name "GPIO13") (class "Default")
      (node (ref "IC5") (pin "P$38") (pinfunction "GPIO1_P$38") (pintype "bidirectional"))
    )
    (net (code "102") (name "GPIO14") (class "Default")
      (node (ref "IC5") (pin "P$2") (pinfunction "GPIO3_P$2") (pintype "bidirectional"))
    )
    (net (code "103") (name "GPIO15") (class "Default")
      (node (ref "IC5") (pin "P$1") (pinfunction "GPIO2_P$1") (pintype "bidirectional"))
    )
    (net (code "104") (name "GPIO16") (class "Default")
      (node (ref "IC4") (pin "P$37") (pinfunction "GPIO0_P$37") (pintype "bidirectional"))
    )
    (net (code "105") (name "GPIO17") (class "Default")
      (node (ref "IC4") (pin "P$38") (pinfunction "GPIO1_P$38") (pintype "bidirectional"))
    )
    (net (code "106") (name "GPIO18") (class "Default")
      (node (ref "IC4") (pin "P$2") (pinfunction "GPIO3_P$2") (pintype "bidirectional"))
    )
    (net (code "107") (name "GPIO19") (class "Default")
      (node (ref "IC4") (pin "P$1") (pinfunction "GPIO2_P$1") (pintype "bidirectional"))
    )
    (net (code "108") (name "GPIO20") (class "Default")
      (node (ref "IC6") (pin "P$37") (pinfunction "GPIO0_P$37") (pintype "bidirectional"))
    )
    (net (code "109") (name "GPIO21") (class "Default")
      (node (ref "IC6") (pin "P$38") (pinfunction "GPIO1_P$38") (pintype "bidirectional"))
    )
    (net (code "110") (name "GPIO22") (class "Default")
      (node (ref "IC6") (pin "P$1") (pinfunction "GPIO2_P$1") (pintype "bidirectional"))
    )
    (net (code "111") (name "GPIO23") (class "Default")
      (node (ref "IC6") (pin "P$2") (pinfunction "GPIO3_P$2") (pintype "bidirectional"))
    )
    (net (code "112") (name "Net-(C32-Pad2)") (class "Default")
      (node (ref "C32") (pin "2") (pinfunction "2_2") (pintype "passive"))
      (node (ref "R7") (pin "2") (pinfunction "2_2") (pintype "passive"))
    )
    (net (code "113") (name "Net-(IC1-NC1)") (class "Default")
      (node (ref "IC1") (pin "P$11") (pinfunction "NC1_P$11") (pintype "bidirectional"))
      (node (ref "IC1") (pin "P$12") (pinfunction "NC2_P$12") (pintype "bidirectional"))
      (node (ref "IC1") (pin "P$13") (pinfunction "NC3_P$13") (pintype "bidirectional"))
      (node (ref "IC1") (pin "P$14") (pinfunction "NC4_P$14") (pintype "bidirectional"))
      (node (ref "R1") (pin "2") (pinfunction "2_2") (pintype "passive"))
    )
    (net (code "114") (name "Net-(IC2-NC1)") (class "Default")
      (node (ref "IC2") (pin "P$11") (pinfunction "NC1_P$11") (pintype "bidirectional"))
      (node (ref "IC2") (pin "P$12") (pinfunction "NC2_P$12") (pintype "bidirectional"))
      (node (ref "IC2") (pin "P$13") (pinfunction "NC3_P$13") (pintype "bidirectional"))
      (node (ref "IC2") (pin "P$14") (pinfunction "NC4_P$14") (pintype "bidirectional"))
      (node (ref "R2") (pin "2") (pinfunction "2_2") (pintype "passive"))
    )
    (net (code "115") (name "Net-(IC3-NC1)") (class "Default")
      (node (ref "IC3") (pin "P$11") (pinfunction "NC1_P$11") (pintype "bidirectional"))
      (node (ref "IC3") (pin "P$12") (pinfunction "NC2_P$12") (pintype "bidirectional"))
      (node (ref "IC3") (pin "P$13") (pinfunction "NC3_P$13") (pintype "bidirectional"))
      (node (ref "IC3") (pin "P$14") (pinfunction "NC4_P$14") (pintype "bidirectional"))
      (node (ref "R3") (pin "2") (pinfunction "2_2") (pintype "passive"))
    )
    (net (code "116") (name "Net-(IC4-NC1)") (class "Default")
      (node (ref "IC4") (pin "P$11") (pinfunction "NC1_P$11") (pintype "bidirectional"))
      (node (ref "IC4") (pin "P$12") (pinfunction "NC2_P$12") (pintype "bidirectional"))
      (node (ref "IC4") (pin "P$13") (pinfunction "NC3_P$13") (pintype "bidirectional"))
      (node (ref "IC4") (pin "P$14") (pinfunction "NC4_P$14") (pintype "bidirectional"))
      (node (ref "R4") (pin "2") (pinfunction "2_2") (pintype "passive"))
    )
    (net (code "117") (name "Net-(IC5-NC1)") (class "Default")
      (node (ref "IC5") (pin "P$11") (pinfunction "NC1_P$11") (pintype "bidirectional"))
      (node (ref "IC5") (pin "P$12") (pinfunction "NC2_P$12") (pintype "bidirectional"))
      (node (ref "IC5") (pin "P$13") (pinfunction "NC3_P$13") (pintype "bidirectional"))
      (node (ref "IC5") (pin "P$14") (pinfunction "NC4_P$14") (pintype "bidirectional"))
      (node (ref "R5") (pin "2") (pinfunction "2_2") (pintype "passive"))
    )
    (net (code "118") (name "Net-(IC6-NC1)") (class "Default")
      (node (ref "IC6") (pin "P$11") (pinfunction "NC1_P$11") (pintype "bidirectional"))
      (node (ref "IC6") (pin "P$12") (pinfunction "NC2_P$12") (pintype "bidirectional"))
      (node (ref "IC6") (pin "P$13") (pinfunction "NC3_P$13") (pintype "bidirectional"))
      (node (ref "IC6") (pin "P$14") (pinfunction "NC4_P$14") (pintype "bidirectional"))
      (node (ref "R6") (pin "2") (pinfunction "2_2") (pintype "passive"))
    )
    (net (code "119") (name "Net-(U$1-TRIM)") (class "Default")
      (node (ref "C30") (pin "1") (pinfunction "1_1") (pintype "passive"))
      (node (ref "U$1") (pin "P$5") (pinfunction "TRIM_P$5") (pintype "bidirectional"))
    )
    (net (code "120") (name "SCLK") (class "Default")
      (node (ref "IC1") (pin "P$32") (pinfunction "SCLK_P$32") (pintype "bidirectional"))
      (node (ref "IC2") (pin "P$32") (pinfunction "SCLK_P$32") (pintype "bidirectional"))
      (node (ref "IC3") (pin "P$32") (pinfunction "SCLK_P$32") (pintype "bidirectional"))
      (node (ref "IC4") (pin "P$32") (pinfunction "SCLK_P$32") (pintype "bidirectional"))
      (node (ref "IC5") (pin "P$32") (pinfunction "SCLK_P$32") (pintype "bidirectional"))
      (node (ref "IC6") (pin "P$32") (pinfunction "SCLK_P$32") (pintype "bidirectional"))
    )
    (net (code "121") (name "SDI") (class "Default")
      (node (ref "IC1") (pin "P$33") (pinfunction "SDI_P$33") (pintype "bidirectional"))
      (node (ref "IC2") (pin "P$33") (pinfunction "SDI_P$33") (pintype "bidirectional"))
      (node (ref "IC3") (pin "P$33") (pinfunction "SDI_P$33") (pintype "bidirectional"))
      (node (ref "IC4") (pin "P$33") (pinfunction "SDI_P$33") (pintype "bidirectional"))
      (node (ref "IC5") (pin "P$33") (pinfunction "SDI_P$33") (pintype "bidirectional"))
      (node (ref "IC6") (pin "P$33") (pinfunction "SDI_P$33") (pintype "bidirectional"))
    )
    (net (code "122") (name "SDO") (class "Default")
      (node (ref "IC1") (pin "P$34") (pinfunction "SDO_P$34") (pintype "bidirectional"))
      (node (ref "IC2") (pin "P$34") (pinfunction "SDO_P$34") (pintype "bidirectional"))
      (node (ref "IC3") (pin "P$34") (pinfunction "SDO_P$34") (pintype "bidirectional"))
      (node (ref "IC4") (pin "P$34") (pinfunction "SDO_P$34") (pintype "bidirectional"))
      (node (ref "IC5") (pin "P$34") (pinfunction "SDO_P$34") (pintype "bidirectional"))
      (node (ref "IC6") (pin "P$34") (pinfunction "SDO_P$34") (pintype "bidirectional"))
    )
    (net (code "123") (name "VA") (class "Default")
      (node (ref "C1") (pin "1") (pinfunction "1_1") (pintype "passive"))
      (node (ref "C11") (pin "1") (pinfunction "1_1") (pintype "passive"))
      (node (ref "C13") (pin "1") (pinfunction "1_1") (pintype "passive"))
      (node (ref "C15") (pin "1") (pinfunction "1_1") (pintype "passive"))
      (node (ref "C17") (pin "1") (pinfunction "1_1") (pintype "passive"))
      (node (ref "C19") (pin "1") (pinfunction "1_1") (pintype "passive"))
      (node (ref "C21") (pin "1") (pinfunction "1_1") (pintype "passive"))
      (node (ref "C23") (pin "1") (pinfunction "1_1") (pintype "passive"))
      (node (ref "C3") (pin "1") (pinfunction "1_1") (pintype "passive"))
      (node (ref "C5") (pin "1") (pinfunction "1_1") (pintype "passive"))
      (node (ref "C7") (pin "1") (pinfunction "1_1") (pintype "passive"))
      (node (ref "C9") (pin "1") (pinfunction "1_1") (pintype "passive"))
      (node (ref "IC1") (pin "P$29") (pinfunction "+VA2_P$29") (pintype "bidirectional"))
      (node (ref "IC1") (pin "P$5") (pinfunction "+VA1_P$5") (pintype "bidirectional"))
      (node (ref "IC2") (pin "P$29") (pinfunction "+VA2_P$29") (pintype "bidirectional"))
      (node (ref "IC2") (pin "P$5") (pinfunction "+VA1_P$5") (pintype "bidirectional"))
      (node (ref "IC3") (pin "P$29") (pinfunction "+VA2_P$29") (pintype "bidirectional"))
      (node (ref "IC3") (pin "P$5") (pinfunction "+VA1_P$5") (pintype "bidirectional"))
      (node (ref "IC4") (pin "P$29") (pinfunction "+VA2_P$29") (pintype "bidirectional"))
      (node (ref "IC4") (pin "P$5") (pinfunction "+VA1_P$5") (pintype "bidirectional"))
      (node (ref "IC5") (pin "P$29") (pinfunction "+VA2_P$29") (pintype "bidirectional"))
      (node (ref "IC5") (pin "P$5") (pinfunction "+VA1_P$5") (pintype "bidirectional"))
      (node (ref "IC6") (pin "P$29") (pinfunction "+VA2_P$29") (pintype "bidirectional"))
      (node (ref "IC6") (pin "P$5") (pinfunction "+VA1_P$5") (pintype "bidirectional"))
      (node (ref "X1") (pin "P$2") (pinfunction "$/1_P$2") (pintype "bidirectional"))
      (node (ref "X10") (pin "P$2") (pinfunction "$/1_P$2") (pintype "bidirectional"))
      (node (ref "X11") (pin "P$2") (pinfunction "$/1_P$2") (pintype "bidirectional"))
      (node (ref "X12") (pin "P$2") (pinfunction "$/1_P$2") (pintype "bidirectional"))
      (node (ref "X13") (pin "P$2") (pinfunction "$/1_P$2") (pintype "bidirectional"))
      (node (ref "X14") (pin "P$2") (pinfunction "$/1_P$2") (pintype "bidirectional"))
      (node (ref "X15") (pin "P$2") (pinfunction "$/1_P$2") (pintype "bidirectional"))
      (node (ref "X16") (pin "P$2") (pinfunction "$/1_P$2") (pintype "bidirectional"))
      (node (ref "X17") (pin "P$2") (pinfunction "$/1_P$2") (pintype "bidirectional"))
      (node (ref "X18") (pin "P$2") (pinfunction "$/1_P$2") (pintype "bidirectional"))
      (node (ref "X2") (pin "P$2") (pinfunction "$/1_P$2") (pintype "bidirectional"))
      (node (ref "X3") (pin "P$2") (pinfunction "$/1_P$2") (pintype "bidirectional"))
      (node (ref "X4") (pin "P$2") (pinfunction "$/1_P$2") (pintype "bidirectional"))
      (node (ref "X5") (pin "P$2") (pinfunction "$/1_P$2") (pintype "bidirectional"))
      (node (ref "X6") (pin "P$2") (pinfunction "$/1_P$2") (pintype "bidirectional"))
      (node (ref "X7") (pin "P$2") (pinfunction "$/1_P$2") (pintype "bidirectional"))
      (node (ref "X8") (pin "P$2") (pinfunction "$/1_P$2") (pintype "bidirectional"))
      (node (ref "X9") (pin "P$2") (pinfunction "$/1_P$2") (pintype "bidirectional"))
    )
    (net (code "124") (name "VCC") (class "Default")
      (node (ref "C12") (pin "1") (pinfunction "1_1") (pintype "passive"))
      (node (ref "C16") (pin "1") (pinfunction "1_1") (pintype "passive"))
      (node (ref "C20") (pin "1") (pinfunction "1_1") (pintype "passive"))
      (node (ref "C24") (pin "1") (pinfunction "1_1") (pintype "passive"))
      (node (ref "C29") (pin "1") (pinfunction "1_1") (pintype "passive"))
      (node (ref "C4") (pin "1") (pinfunction "1_1") (pintype "passive"))
      (node (ref "C8") (pin "1") (pinfunction "1_1") (pintype "passive"))
      (node (ref "IC1") (pin "P$36") (pinfunction "+VBD_P$36") (pintype "bidirectional"))
      (node (ref "IC2") (pin "P$36") (pinfunction "+VBD_P$36") (pintype "bidirectional"))
      (node (ref "IC3") (pin "P$36") (pinfunction "+VBD_P$36") (pintype "bidirectional"))
      (node (ref "IC4") (pin "P$36") (pinfunction "+VBD_P$36") (pintype "bidirectional"))
      (node (ref "IC5") (pin "P$36") (pinfunction "+VBD_P$36") (pintype "bidirectional"))
      (node (ref "IC6") (pin "P$36") (pinfunction "+VBD_P$36") (pintype "bidirectional"))
      (node (ref "U$1") (pin "P$2") (pinfunction "VIN_P$2") (pintype "bidirectional"))
    )
    (net (code "125") (name "unconnected-(U$1-DNC0-PadP$1)") (class "Default")
      (node (ref "U$1") (pin "P$1") (pinfunction "DNC0_P$1") (pintype "bidirectional"))
    )
    (net (code "126") (name "unconnected-(U$1-DNC1-PadP$8)") (class "Default")
      (node (ref "U$1") (pin "P$8") (pinfunction "DNC1_P$8") (pintype "bidirectional"))
    )
    (net (code "127") (name "unconnected-(U$1-NC-PadP$7)") (class "Default")
      (node (ref "U$1") (pin "P$7") (pinfunction "NC_P$7") (pintype "bidirectional"))
    )
    (net (code "128") (name "unconnected-(U$1-TEMP-PadP$3)") (class "Default")
      (node (ref "U$1") (pin "P$3") (pinfunction "TEMP_P$3") (pintype "bidirectional"))
    )
  )
)
